# VCO.net
KiCad netlist of a schematic drawn in Altium Designer
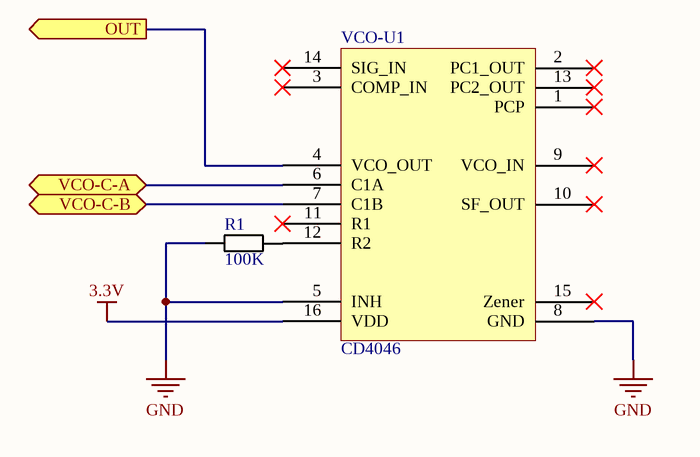
[diagram p0: VCO.SchDoc]

(export (version "E")
  (design (tool "Eeschema 10.0.6"))
  (components
    (comp (ref "R1")
      (value "100K")
      (footprint "R 0805 / 2012")
      (libsource (lib "Standard") (part "Resistor"))
    )
    (comp (ref "VCO-U1")
      (value "CD4046")
      (footprint "SOIC-16")
      (description "PLL / VCO")
      (libsource (lib "ICs") (part "CD4046"))
    )
  )
  (nets
    (net (code "1") (name "/OUT") (class "Default")
      (node (ref "VCO-U1") (pin "4") (pinfunction "VCO_OUT_4") (pintype "passive"))
    )
    (net (code "2") (name "/VCO-C-A") (class "Default")
      (node (ref "VCO-U1") (pin "6") (pinfunction "C1A_6") (pintype "passive"))
    )
    (net (code "3") (name "/VCO-C-B") (class "Default")
      (node (ref "VCO-U1") (pin "7") (pinfunction "C1B_7") (pintype "passive"))
    )
    (net (code "4") (name "3.3V") (class "Default")
      (node (ref "VCO-U1") (pin "16") (pinfunction "VDD_16") (pintype "passive"))
    )
    (net (code "5") (name "GND") (class "Default")
      (node (ref "R1") (pin "2") (pinfunction "2_2") (pintype "passive"))
      (node (ref "VCO-U1") (pin "5") (pinfunction "INH_5") (pintype "passive"))
      (node (ref "VCO-U1") (pin "8") (pinfunction "GND_8") (pintype "passive"))
    )
    (net (code "6") (name "Net-(VCO-U1-R2)") (class "Default")
      (node (ref "R1") (pin "1") (pinfunction "1_1") (pintype "passive"))
      (node (ref "VCO-U1") (pin "12") (pinfunction "R2_12") (pintype "passive"))
    )
    (net (code "7") (name "unconnected-(VCO-U1-COMP_IN-Pad3)") (class "Default")
      (node (ref "VCO-U1") (pin "3") (pinfunction "COMP_IN_3") (pintype "passive+no_connect"))
    )
    (net (code "8") (name "unconnected-(VCO-U1-PC1_OUT-Pad2)") (class "Default")
      (node (ref "VCO-U1") (pin "2") (pinfunction "PC1_OUT_2") (pintype "passive+no_connect"))
    )
    (net (code "9") (name "unconnected-(VCO-U1-PC2_OUT-Pad13)") (class "Default")
      (node (ref "VCO-U1") (pin "13") (pinfunction "PC2_OUT_13") (pintype "passive+no_connect"))
    )
    (net (code "10") (name "unconnected-(VCO-U1-PCP-Pad1)") (class "Default")
      (node (ref "VCO-U1") (pin "1") (pinfunction "PCP_1") (pintype "passive+no_connect"))
    )
    (net (code "11") (name "unconnected-(VCO-U1-R1-Pad11)") (class "Default")
      (node (ref "VCO-U1") (pin "11") (pinfunction "R1_11") (pintype "passive+no_connect"))
    )
    (net (code "12") (name "unconnected-(VCO-U1-SF_OUT-Pad10)") (class "Default")
      (node (ref "VCO-U1") (pin "10") (pinfunction "SF_OUT_10") (pintype "passive+no_connect"))
    )
    (net (code "13") (name "unconnected-(VCO-U1-SIG_IN-Pad14)") (class "Default")
      (node (ref "VCO-U1") (pin "14") (pinfunction "SIG_IN_14") (pintype "passive+no_connect"))
    )
    (net (code "14") (name "unconnected-(VCO-U1-VCO_IN-Pad9)") (class "Default")
      (node (ref "VCO-U1") (pin "9") (pinfunction "VCO_IN_9") (pintype "passive+no_connect"))
    )
    (net (code "15") (name "unconnected-(VCO-U1-Zener-Pad15)") (class "Default")
      (node (ref "VCO-U1") (pin "15") (pinfunction "Zener_15") (pintype "passive+no_connect"))
    )
  )
)
